# LED_Sequencer.net
KiCad netlist of a schematic drawn in Altium Designer
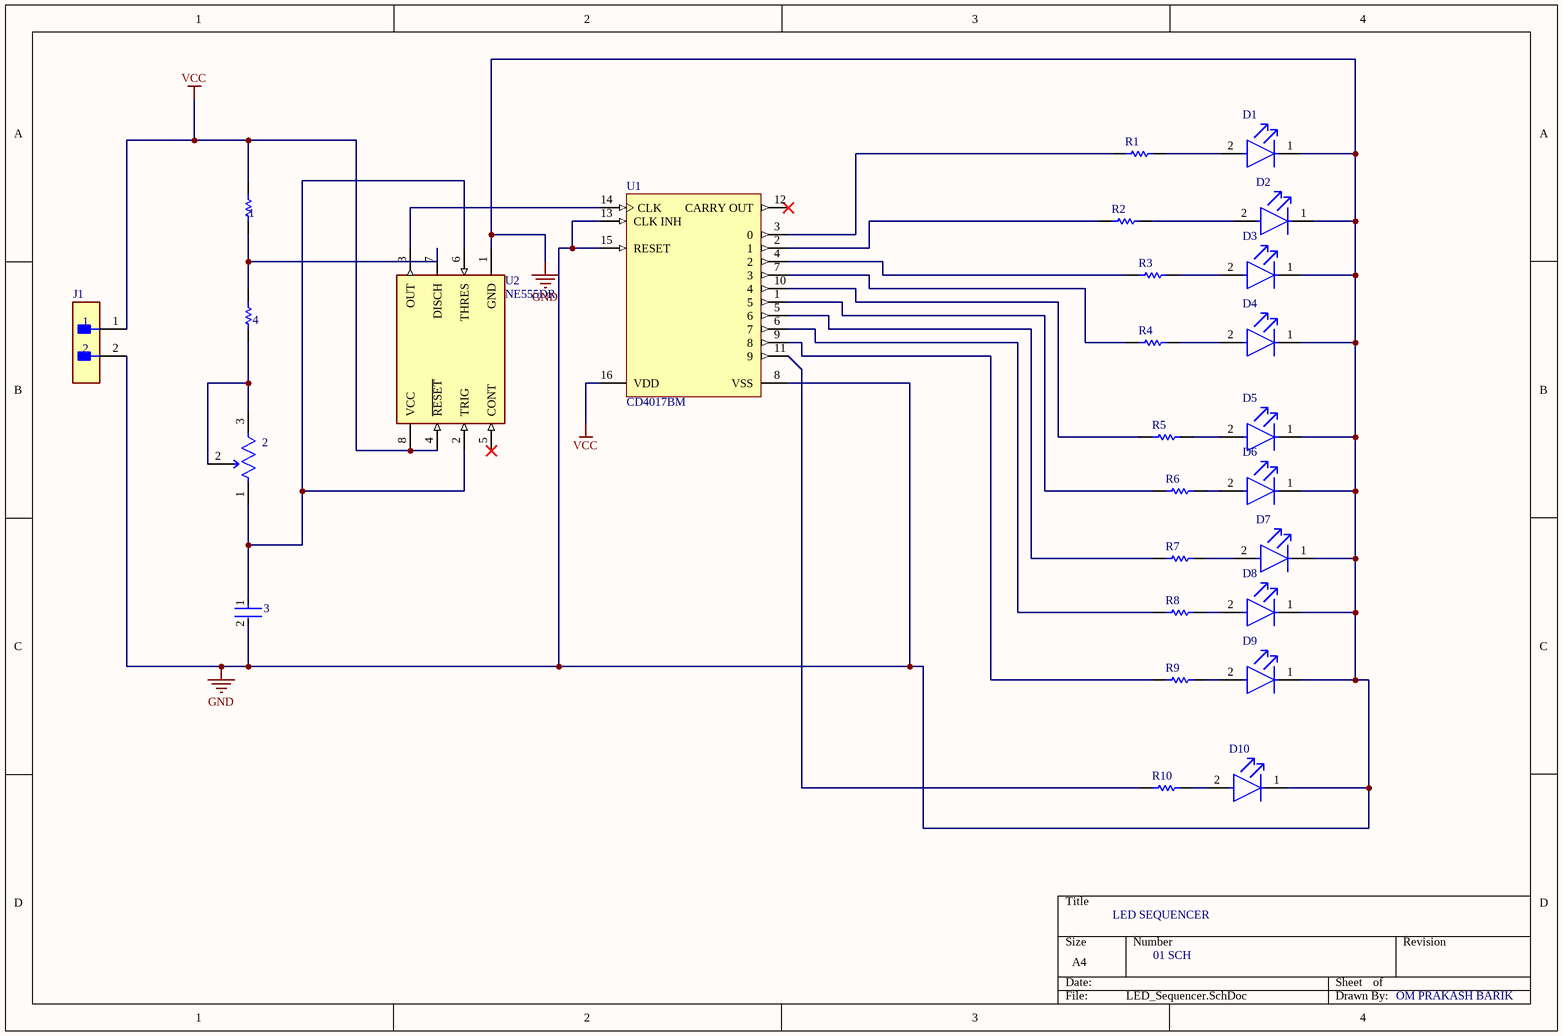
[diagram p0: LED_Sequencer.SchDoc]

(export (version "E")
  (design (tool "Eeschema 10.0.6"))
  (components
    (comp (ref "1")
      (value "ERJ-8ENF1001V")
      (footprint "RESC3216X70X50LL05T20")
      (fields (field (name "MANUFACTURER") "Panasonic"))
      (libsource (lib "Altium Content Vault") (part "RES"))
    )
    (comp (ref "2")
      (value "3386P-1-104LF")
      (footprint "FP-3386P-MFG")
      (description "TRIMMER 100K OHM 0.5W PC PIN TOP")
      (fields (field (name "TOLERANCE") "10%"))
      (libsource (lib "Altium Content Vault") (part "13357d81287629c2fd191d242cfa50c"))
    )
    (comp (ref "3")
      (value "C2012X5R1E105K125AA")
      (footprint "FP-C2012-125-0_2-IPC_A")
      (description "Multilayer Ceramic Capacitors 1μF ±10% 25V X5R SMD 0805")
      (fields (field (name "VOLTAGE") "25V") (field (name "TOLERANCE") "10%"))
      (libsource (lib "Altium Content Vault") (part "b4654b650e69147ec39a6b967a45e02"))
    )
    (comp (ref "4")
      (value "ERJ-8ENF1001V")
      (footprint "RESC3216X70X50LL05T20")
      (fields (field (name "MANUFACTURER") "Panasonic"))
      (libsource (lib "Altium Content Vault") (part "RES"))
    )
    (comp (ref "D1")
      (value "HLMP-1719")
      (footprint "FP-HLMP-1719-MFG")
      (description "LED YELLOW DIFFUSED T-1 T/H")
      (fields
        (field (name "MANUFACTURER") "Broadcom")
        (field (name "OCTOPART") "https://octopart.com/hlmp-1719-broadcom-71130405")
      )
      (libsource (lib "Altium Content Vault") (part "8706943c75ba83719d021d2fdc84c58"))
    )
    (comp (ref "D2")
      (value "HLMP-1719")
      (footprint "FP-HLMP-1719-MFG")
      (description "LED YELLOW DIFFUSED T-1 T/H")
      (fields
        (field (name "MANUFACTURER") "Broadcom")
        (field (name "OCTOPART") "https://octopart.com/hlmp-1719-broadcom-71130405")
      )
      (libsource (lib "Altium Content Vault") (part "8706943c75ba83719d021d2fdc84c58"))
    )
    (comp (ref "D3")
      (value "HLMP-1719")
      (footprint "FP-HLMP-1719-MFG")
      (description "LED YELLOW DIFFUSED T-1 T/H")
      (fields
        (field (name "MANUFACTURER") "Broadcom")
        (field (name "OCTOPART") "https://octopart.com/hlmp-1719-broadcom-71130405")
      )
      (libsource (lib "Altium Content Vault") (part "8706943c75ba83719d021d2fdc84c58"))
    )
    (comp (ref "D4")
      (value "HLMP-1719")
      (footprint "FP-HLMP-1719-MFG")
      (description "LED YELLOW DIFFUSED T-1 T/H")
      (fields
        (field (name "MANUFACTURER") "Broadcom")
        (field (name "OCTOPART") "https://octopart.com/hlmp-1719-broadcom-71130405")
      )
      (libsource (lib "Altium Content Vault") (part "8706943c75ba83719d021d2fdc84c58"))
    )
    (comp (ref "D5")
      (value "HLMP-1719")
      (footprint "FP-HLMP-1719-MFG")
      (description "LED YELLOW DIFFUSED T-1 T/H")
      (fields
        (field (name "MANUFACTURER") "Broadcom")
        (field (name "OCTOPART") "https://octopart.com/hlmp-1719-broadcom-71130405")
      )
      (libsource (lib "Altium Content Vault") (part "8706943c75ba83719d021d2fdc84c58"))
    )
    (comp (ref "D6")
      (value "HLMP-1719")
      (footprint "FP-HLMP-1719-MFG")
      (description "LED YELLOW DIFFUSED T-1 T/H")
      (fields
        (field (name "MANUFACTURER") "Broadcom")
        (field (name "OCTOPART") "https://octopart.com/hlmp-1719-broadcom-71130405")
      )
      (libsource (lib "Altium Content Vault") (part "8706943c75ba83719d021d2fdc84c58"))
    )
    (comp (ref "D7")
      (value "HLMP-1719")
      (footprint "FP-HLMP-1719-MFG")
      (description "LED YELLOW DIFFUSED T-1 T/H")
      (fields
        (field (name "MANUFACTURER") "Broadcom")
        (field (name "OCTOPART") "https://octopart.com/hlmp-1719-broadcom-71130405")
      )
      (libsource (lib "Altium Content Vault") (part "8706943c75ba83719d021d2fdc84c58"))
    )
    (comp (ref "D8")
      (value "HLMP-1719")
      (footprint "FP-HLMP-1719-MFG")
      (description "LED YELLOW DIFFUSED T-1 T/H")
      (fields
        (field (name "MANUFACTURER") "Broadcom")
        (field (name "OCTOPART") "https://octopart.com/hlmp-1719-broadcom-71130405")
      )
      (libsource (lib "Altium Content Vault") (part "8706943c75ba83719d021d2fdc84c58"))
    )
    (comp (ref "D9")
      (value "HLMP-1719")
      (footprint "FP-HLMP-1719-MFG")
      (description "LED YELLOW DIFFUSED T-1 T/H")
      (fields
        (field (name "MANUFACTURER") "Broadcom")
        (field (name "OCTOPART") "https://octopart.com/hlmp-1719-broadcom-71130405")
      )
      (libsource (lib "Altium Content Vault") (part "8706943c75ba83719d021d2fdc84c58"))
    )
    (comp (ref "D10")
      (value "HLMP-1719")
      (footprint "FP-HLMP-1719-MFG")
      (description "LED YELLOW DIFFUSED T-1 T/H")
      (fields
        (field (name "MANUFACTURER") "Broadcom")
        (field (name "OCTOPART") "https://octopart.com/hlmp-1719-broadcom-71130405")
      )
      (libsource (lib "Altium Content Vault") (part "8706943c75ba83719d021d2fdc84c58"))
    )
    (comp (ref "J1")
      (value "M20-9990245")
      (footprint "FP-M20-9990245-MFG")
      (description "CONN HEADER VERT 2POS 2.54MM")
      (fields (field (name "VOLTAGE") "50V"))
      (libsource (lib "Altium Content Vault") (part "3bc925449376181038e59eaffc5286c"))
    )
    (comp (ref "R1")
      (value "ERJ-8ENF1001V")
      (footprint "RESC3216X70X50LL05T20")
      (fields (field (name "MANUFACTURER") "Panasonic"))
      (libsource (lib "Altium Content Vault") (part "RES"))
    )
    (comp (ref "R2")
      (value "ERJ-8ENF1001V")
      (footprint "RESC3216X70X50LL05T20")
      (fields (field (name "MANUFACTURER") "Panasonic"))
      (libsource (lib "Altium Content Vault") (part "RES"))
    )
    (comp (ref "R3")
      (value "ERJ-8ENF1001V")
      (footprint "RESC3216X70X50LL05T20")
      (fields (field (name "MANUFACTURER") "Panasonic"))
      (libsource (lib "Altium Content Vault") (part "RES"))
    )
    (comp (ref "R4")
      (value "ERJ-8ENF1001V")
      (footprint "RESC3216X70X50LL05T20")
      (fields (field (name "MANUFACTURER") "Panasonic"))
      (libsource (lib "Altium Content Vault") (part "RES"))
    )
    (comp (ref "R5")
      (value "ERJ-8ENF1001V")
      (footprint "RESC3216X70X50LL05T20")
      (fields (field (name "MANUFACTURER") "Panasonic"))
      (libsource (lib "Altium Content Vault") (part "RES"))
    )
    (comp (ref "R6")
      (value "ERJ-8ENF1001V")
      (footprint "RESC3216X70X50LL05T20")
      (fields (field (name "MANUFACTURER") "Panasonic"))
      (libsource (lib "Altium Content Vault") (part "RES"))
    )
    (comp (ref "R7")
      (value "ERJ-8ENF1001V")
      (footprint "RESC3216X70X50LL05T20")
      (fields (field (name "MANUFACTURER") "Panasonic"))
      (libsource (lib "Altium Content Vault") (part "RES"))
    )
    (comp (ref "R8")
      (value "ERJ-8ENF1001V")
      (footprint "RESC3216X70X50LL05T20")
      (fields (field (name "MANUFACTURER") "Panasonic"))
      (libsource (lib "Altium Content Vault") (part "RES"))
    )
    (comp (ref "R9")
      (value "ERJ-8ENF1001V")
      (footprint "RESC3216X70X50LL05T20")
      (fields (field (name "MANUFACTURER") "Panasonic"))
      (libsource (lib "Altium Content Vault") (part "RES"))
    )
    (comp (ref "R10")
      (value "ERJ-8ENF1001V")
      (footprint "RESC3216X70X50LL05T20")
      (fields (field (name "MANUFACTURER") "Panasonic"))
      (libsource (lib "Altium Content Vault") (part "RES"))
    )
    (comp (ref "U1")
      (value "CD4017BM")
      (footprint "D0016A_N")
      (description "CMOS Decade Counter with 10 Decoded Outputs, D0016A, TUBE")
      (fields
        (field (name "GENERIC PART NUMBER") "CD4017B")
        (field (name "MANUFACTURER") "Texas Instruments")
      )
      (libsource (lib "Altium Content Vault") (part "TI-CD4017B-16"))
    )
    (comp (ref "U2")
      (value "NE555DR")
      (footprint "FP-D0008A-IPC_A")
      (description "IC OSC SGL TIMER 100KHZ 8-SOIC")
      (libsource (lib "Altium Content Vault") (part "a29bba90211dec1890110b94dad7d53"))
    )
  )
  (nets
    (net (code "1") (name "GND") (class "Default")
      (node (ref "3") (pin "2") (pinfunction "2_2") (pintype "passive"))
      (node (ref "D1") (pin "1") (pinfunction "C_1") (pintype "passive"))
      (node (ref "D10") (pin "1") (pinfunction "C_1") (pintype "passive"))
      (node (ref "D2") (pin "1") (pinfunction "C_1") (pintype "passive"))
      (node (ref "D3") (pin "1") (pinfunction "C_1") (pintype "passive"))
      (node (ref "D4") (pin "1") (pinfunction "C_1") (pintype "passive"))
      (node (ref "D5") (pin "1") (pinfunction "C_1") (pintype "passive"))
      (node (ref "D6") (pin "1") (pinfunction "C_1") (pintype "passive"))
      (node (ref "D7") (pin "1") (pinfunction "C_1") (pintype "passive"))
      (node (ref "D8") (pin "1") (pinfunction "C_1") (pintype "passive"))
      (node (ref "D9") (pin "1") (pinfunction "C_1") (pintype "passive"))
      (node (ref "J1") (pin "2") (pinfunction "2_2") (pintype "passive"))
      (node (ref "U1") (pin "13") (pinfunction "CLK_INH_13") (pintype "input"))
      (node (ref "U1") (pin "15") (pinfunction "RESET_15") (pintype "input"))
      (node (ref "U1") (pin "8") (pinfunction "VSS_8") (pintype "power_in"))
      (node (ref "U2") (pin "1") (pinfunction "GND_1") (pintype "power_in"))
    )
    (net (code "2") (name "Net-(2-CCW)") (class "Default")
      (node (ref "2") (pin "1") (pinfunction "CCW_1") (pintype "passive"))
      (node (ref "3") (pin "1") (pinfunction "1_1") (pintype "passive"))
      (node (ref "U2") (pin "2") (pinfunction "TRIG_2") (pintype "input"))
      (node (ref "U2") (pin "6") (pinfunction "THRES_6") (pintype "input"))
    )
    (net (code "3") (name "Net-(2-CW)") (class "Default")
      (node (ref "2") (pin "2") (pinfunction "WIPER_2") (pintype "passive"))
      (node (ref "2") (pin "3") (pinfunction "CW_3") (pintype "passive"))
      (node (ref "4") (pin "2") (pinfunction "2_2") (pintype "passive"))
    )
    (net (code "4") (name "Net-(D1-A)") (class "Default")
      (node (ref "D1") (pin "2") (pinfunction "A_2") (pintype "passive"))
      (node (ref "R1") (pin "2") (pinfunction "2_2") (pintype "passive"))
    )
    (net (code "5") (name "Net-(D2-A)") (class "Default")
      (node (ref "D2") (pin "2") (pinfunction "A_2") (pintype "passive"))
      (node (ref "R2") (pin "2") (pinfunction "2_2") (pintype "passive"))
    )
    (net (code "6") (name "Net-(D3-A)") (class "Default")
      (node (ref "D3") (pin "2") (pinfunction "A_2") (pintype "passive"))
      (node (ref "R3") (pin "2") (pinfunction "2_2") (pintype "passive"))
    )
    (net (code "7") (name "Net-(D4-A)") (class "Default")
      (node (ref "D4") (pin "2") (pinfunction "A_2") (pintype "passive"))
      (node (ref "R4") (pin "2") (pinfunction "2_2") (pintype "passive"))
    )
    (net (code "8") (name "Net-(D5-A)") (class "Default")
      (node (ref "D5") (pin "2") (pinfunction "A_2") (pintype "passive"))
      (node (ref "R5") (pin "2") (pinfunction "2_2") (pintype "passive"))
    )
    (net (code "9") (name "Net-(D6-A)") (class "Default")
      (node (ref "D6") (pin "2") (pinfunction "A_2") (pintype "passive"))
      (node (ref "R6") (pin "2") (pinfunction "2_2") (pintype "passive"))
    )
    (net (code "10") (name "Net-(D7-A)") (class "Default")
      (node (ref "D7") (pin "2") (pinfunction "A_2") (pintype "passive"))
      (node (ref "R7") (pin "2") (pinfunction "2_2") (pintype "passive"))
    )
    (net (code "11") (name "Net-(D8-A)") (class "Default")
      (node (ref "D8") (pin "2") (pinfunction "A_2") (pintype "passive"))
      (node (ref "R8") (pin "2") (pinfunction "2_2") (pintype "passive"))
    )
    (net (code "12") (name "Net-(D9-A)") (class "Default")
      (node (ref "D9") (pin "2") (pinfunction "A_2") (pintype "passive"))
      (node (ref "R9") (pin "2") (pinfunction "2_2") (pintype "passive"))
    )
    (net (code "13") (name "Net-(D10-A)") (class "Default")
      (node (ref "D10") (pin "2") (pinfunction "A_2") (pintype "passive"))
      (node (ref "R10") (pin "2") (pinfunction "2_2") (pintype "passive"))
    )
    (net (code "14") (name "Net-(U1-0)") (class "Default")
      (node (ref "R1") (pin "1") (pinfunction "1_1") (pintype "passive"))
      (node (ref "U1") (pin "3") (pinfunction "0_3") (pintype "output"))
    )
    (net (code "15") (name "Net-(U1-1)") (class "Default")
      (node (ref "R2") (pin "1") (pinfunction "1_1") (pintype "passive"))
      (node (ref "U1") (pin "2") (pinfunction "1_2") (pintype "output"))
    )
    (net (code "16") (name "Net-(U1-2)") (class "Default")
      (node (ref "R3") (pin "1") (pinfunction "1_1") (pintype "passive"))
      (node (ref "U1") (pin "4") (pinfunction "2_4") (pintype "output"))
    )
    (net (code "17") (name "Net-(U1-3)") (class "Default")
      (node (ref "R4") (pin "1") (pinfunction "1_1") (pintype "passive"))
      (node (ref "U1") (pin "7") (pinfunction "3_7") (pintype "output"))
    )
    (net (code "18") (name "Net-(U1-4)") (class "Default")
      (node (ref "R5") (pin "1") (pinfunction "1_1") (pintype "passive"))
      (node (ref "U1") (pin "10") (pinfunction "4_10") (pintype "output"))
    )
    (net (code "19") (name "Net-(U1-5)") (class "Default")
      (node (ref "R6") (pin "1") (pinfunction "1_1") (pintype "passive"))
      (node (ref "U1") (pin "1") (pinfunction "5_1") (pintype "output"))
    )
    (net (code "20") (name "Net-(U1-6)") (class "Default")
      (node (ref "R7") (pin "1") (pinfunction "1_1") (pintype "passive"))
      (node (ref "U1") (pin "5") (pinfunction "6_5") (pintype "output"))
    )
    (net (code "21") (name "Net-(U1-7)") (class "Default")
      (node (ref "R8") (pin "1") (pinfunction "1_1") (pintype "passive"))
      (node (ref "U1") (pin "6") (pinfunction "7_6") (pintype "output"))
    )
    (net (code "22") (name "Net-(U1-8)") (class "Default")
      (node (ref "R9") (pin "1") (pinfunction "1_1") (pintype "passive"))
      (node (ref "U1") (pin "9") (pinfunction "8_9") (pintype "output"))
    )
    (net (code "23") (name "Net-(U1-9)") (class "Default")
      (node (ref "R10") (pin "1") (pinfunction "1_1") (pintype "passive"))
      (node (ref "U1") (pin "11") (pinfunction "9_11") (pintype "output"))
    )
    (net (code "24") (name "Net-(U1-CLK)") (class "Default")
      (node (ref "U1") (pin "14") (pinfunction "CLK_14") (pintype "input"))
      (node (ref "U2") (pin "3") (pinfunction "OUT_3") (pintype "output"))
    )
    (net (code "25") (name "Net-(U2-DISCH)") (class "Default")
      (node (ref "1") (pin "2") (pinfunction "2_2") (pintype "passive"))
      (node (ref "4") (pin "1") (pinfunction "1_1") (pintype "passive"))
      (node (ref "U2") (pin "7") (pinfunction "DISCH_7") (pintype "open_collector"))
    )
    (net (code "26") (name "VCC") (class "Default")
      (node (ref "1") (pin "1") (pinfunction "1_1") (pintype "passive"))
      (node (ref "J1") (pin "1") (pinfunction "1_1") (pintype "passive"))
      (node (ref "U1") (pin "16") (pinfunction "VDD_16") (pintype "power_in"))
      (node (ref "U2") (pin "4") (pinfunction "~{RESET}_4") (pintype "input"))
      (node (ref "U2") (pin "8") (pinfunction "VCC_8") (pintype "power_in"))
    )
    (net (code "27") (name "unconnected-(U1-CARRY_OUT-Pad12)") (class "Default")
      (node (ref "U1") (pin "12") (pinfunction "CARRY_OUT_12") (pintype "output+no_connect"))
    )
    (net (code "28") (name "unconnected-(U2-CONT-Pad5)") (class "Default")
      (node (ref "U2") (pin "5") (pinfunction "CONT_5") (pintype "input+no_connect"))
    )
  )
)
